# rp3a0-mini-hdmi.net
KiCad netlist of a schematic drawn in Altium Designer
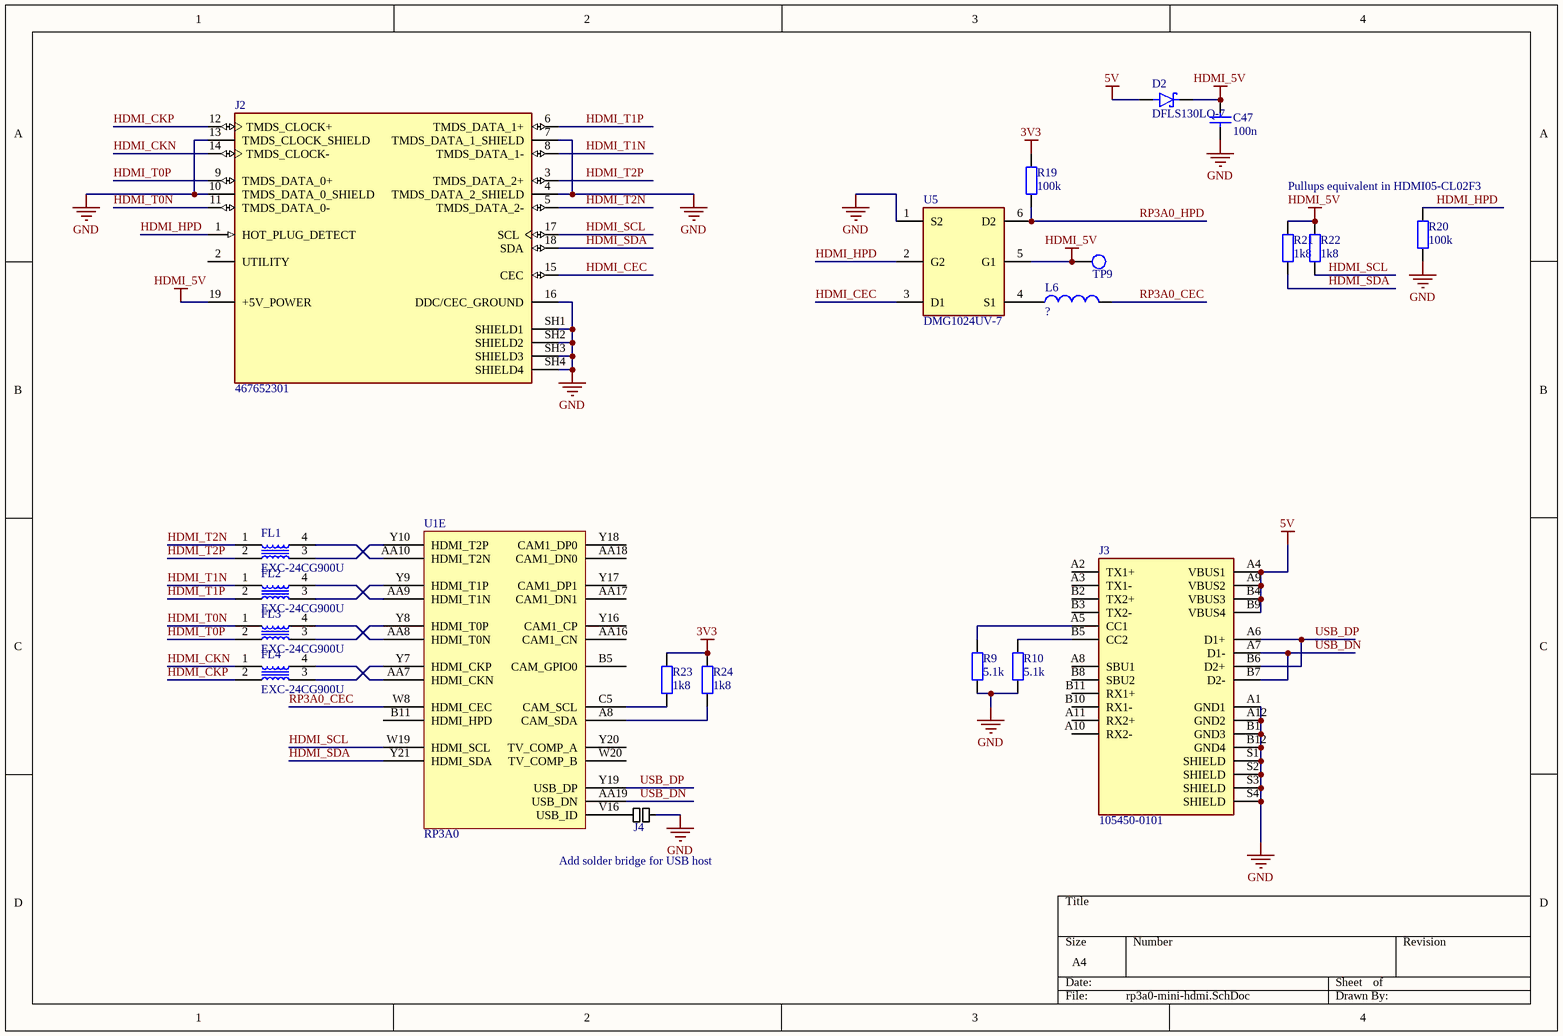
[diagram p0: rp3a0-mini-hdmi.SchDoc]

(export (version "E")
  (design (tool "Eeschema 10.0.6"))
  (components
    (comp (ref "C47")
      (value "100n")
      (footprint "0402")
      (description "Capacitor")
      (fields (field (name "Comment") "Cap"))
      (libsource (lib "custom-lib") (part "CAP-NONPOL"))
    )
    (comp (ref "D2")
      (value "DFLS130LQ-7")
      (footprint "DIO_DFLS130LQ-7")
      (description "Diode Schottky 1A 30V PowerDI 123 ¦ Diodes Inc DFLS130LQ-7")
      (fields (field (name "MF") "Diodes Inc.") (field (name "MP") "DFLS1100-7"))
      (libsource (lib "custom-lib") (part "DFLS130LQ-7"))
    )
    (comp (ref "FL1")
      (value "EXC-24CG900U")
      (footprint "FIL_EXC24CB102U")
      (fields (field (name "MP") "EXC24CG900U") (field (name "MF") "Panasonic"))
      (libsource (lib "panasonic") (part "EXC-24CG900U"))
    )
    (comp (ref "FL2")
      (value "EXC-24CG900U")
      (footprint "FIL_EXC24CB102U")
      (fields (field (name "MP") "EXC24CG900U") (field (name "MF") "Panasonic"))
      (libsource (lib "panasonic") (part "EXC-24CG900U"))
    )
    (comp (ref "FL3")
      (value "EXC-24CG900U")
      (footprint "FIL_EXC24CB102U")
      (fields (field (name "MP") "EXC24CG900U") (field (name "MF") "Panasonic"))
      (libsource (lib "panasonic") (part "EXC-24CG900U"))
    )
    (comp (ref "FL4")
      (value "EXC-24CG900U")
      (footprint "FIL_EXC24CB102U")
      (fields (field (name "MP") "EXC24CG900U") (field (name "MF") "Panasonic"))
      (libsource (lib "panasonic") (part "EXC-24CG900U"))
    )
    (comp (ref "J2")
      (value "467652301")
      (footprint "MOLEX_467652301")
      (fields (field (name "MF") "Molex"))
      (libsource (lib "custom-lib") (part "467652301"))
    )
    (comp (ref "J3")
      (value "105450-0101")
      (footprint "MOLEX_105450-0101")
      (description "USB-C, USB 3.1 Gen 2, Receptacle Connector 24 Position Surface Mount, Right Angle; Through Hole")
      (fields (field (name "MF") "Molex") (field (name "DIGI-KEY_PART_NUMBER") "WM12856CT-ND"))
      (libsource (lib "custom-lib") (part "105450-0101"))
    )
    (comp (ref "J4")
      (value "SOLDER_PAD_OPEN")
      (footprint "SOLDER_PAD_OPEN")
      (description "Solder pads with no connection")
      (libsource (lib "custom-lib") (part "SOLDER_PAD_OPEN"))
    )
    (comp (ref "L6")
      (value "?")
      (footprint "0402")
      (description "Inductor SMD")
      (fields (field (name "Comment") "INDUCTOR"))
      (libsource (lib "custom-lib") (part "INDUCTOR"))
    )
    (comp (ref "R9")
      (value "5.1k")
      (footprint "RES-0402-SML")
      (description "Resistor")
      (fields (field (name "Comment") "Res SMD"))
      (libsource (lib "custom-lib") (part "Res SMD"))
    )
    (comp (ref "R10")
      (value "5.1k")
      (footprint "RES-0402-SML")
      (description "Resistor")
      (fields (field (name "Comment") "Res SMD"))
      (libsource (lib "custom-lib") (part "Res SMD"))
    )
    (comp (ref "R19")
      (value "100k")
      (footprint "RES-0402-SML")
      (description "Resistor")
      (fields (field (name "Comment") "Res SMD"))
      (libsource (lib "custom-lib") (part "Res SMD"))
    )
    (comp (ref "R20")
      (value "100k")
      (footprint "RES-0402-SML")
      (description "Resistor")
      (fields (field (name "Comment") "Res SMD"))
      (libsource (lib "custom-lib") (part "Res SMD"))
    )
    (comp (ref "R21")
      (value "1k8")
      (footprint "RES-0402-SML")
      (description "Resistor")
      (fields (field (name "Comment") "Res SMD"))
      (libsource (lib "custom-lib") (part "Res SMD"))
    )
    (comp (ref "R22")
      (value "1k8")
      (footprint "RES-0402-SML")
      (description "Resistor")
      (fields (field (name "Comment") "Res SMD"))
      (libsource (lib "custom-lib") (part "Res SMD"))
    )
    (comp (ref "R23")
      (value "1k8")
      (footprint "RES-0402-SML")
      (description "Resistor")
      (fields (field (name "Comment") "Res SMD"))
      (libsource (lib "custom-lib") (part "Res SMD"))
    )
    (comp (ref "R24")
      (value "1k8")
      (footprint "RES-0402-SML")
      (description "Resistor")
      (fields (field (name "Comment") "Res SMD"))
      (libsource (lib "custom-lib") (part "Res SMD"))
    )
    (comp (ref "TP9")
      (value "TEST_POINT")
      (footprint "TEST_POINT_1.2MM")
      (description "Test point")
      (libsource (lib "custom-lib") (part "TEST_POINT"))
    )
    (comp (ref "U1") (value "RP3A0") (footprint "RP3A0-BGA") (libsource (lib "rp3a0") (part "RP3A0")))
    (comp (ref "U5")
      (value "DMG1024UV-7")
      (footprint "SOT50P162X60-6N")
      (description "Dual N-Ch Enhancement MOSFET SOT-563 ¦ Diodes Inc DMG1024UV-7")
      (fields (field (name "MF") "Diodes Inc."))
      (libsource (lib "custom-lib") (part "DMG1024UV-7"))
    )
  )
  (nets
    (net (code "1") (name "/HDMI_CEC") (class "Default")
      (node (ref "J2") (pin "15") (pinfunction "CEC_15") (pintype "bidirectional"))
      (node (ref "U5") (pin "3") (pinfunction "D1_3") (pintype "passive"))
    )
    (net (code "2") (name "/HDMI_CKN") (class "Default")
      (node (ref "FL4") (pin "1") (pinfunction "1_1") (pintype "passive"))
      (node (ref "J2") (pin "14") (pinfunction "TMDS_CLOCK-_14") (pintype "bidirectional"))
    )
    (net (code "3") (name "/HDMI_CKP") (class "Default")
      (node (ref "FL4") (pin "2") (pinfunction "2_2") (pintype "passive"))
      (node (ref "J2") (pin "12") (pinfunction "TMDS_CLOCK+_12") (pintype "bidirectional"))
    )
    (net (code "4") (name "/HDMI_HPD") (class "Default")
      (node (ref "J2") (pin "1") (pinfunction "HOT_PLUG_DETECT_1") (pintype "input"))
      (node (ref "R20") (pin "2") (pinfunction "2_2") (pintype "passive"))
      (node (ref "U5") (pin "2") (pinfunction "G2_2") (pintype "passive"))
    )
    (net (code "5") (name "/HDMI_SCL") (class "Default")
      (node (ref "J2") (pin "17") (pinfunction "SCL_17") (pintype "bidirectional"))
      (node (ref "R22") (pin "1") (pinfunction "1_1") (pintype "passive"))
      (node (ref "U1") (pin "W19") (pinfunction "HDMI_SCL_W19") (pintype "passive"))
    )
    (net (code "6") (name "/HDMI_SDA") (class "Default")
      (node (ref "J2") (pin "18") (pinfunction "SDA_18") (pintype "bidirectional"))
      (node (ref "R21") (pin "1") (pinfunction "1_1") (pintype "passive"))
      (node (ref "U1") (pin "Y21") (pinfunction "HDMI_SDA_Y21") (pintype "passive"))
    )
    (net (code "7") (name "/HDMI_T0N") (class "Default")
      (node (ref "FL3") (pin "1") (pinfunction "1_1") (pintype "passive"))
      (node (ref "J2") (pin "11") (pinfunction "TMDS_DATA_0-_11") (pintype "bidirectional"))
    )
    (net (code "8") (name "/HDMI_T0P") (class "Default")
      (node (ref "FL3") (pin "2") (pinfunction "2_2") (pintype "passive"))
      (node (ref "J2") (pin "9") (pinfunction "TMDS_DATA_0+_9") (pintype "bidirectional"))
    )
    (net (code "9") (name "/HDMI_T1N") (class "Default")
      (node (ref "FL2") (pin "1") (pinfunction "1_1") (pintype "passive"))
      (node (ref "J2") (pin "8") (pinfunction "TMDS_DATA_1-_8") (pintype "bidirectional"))
    )
    (net (code "10") (name "/HDMI_T1P") (class "Default")
      (node (ref "FL2") (pin "2") (pinfunction "2_2") (pintype "passive"))
      (node (ref "J2") (pin "6") (pinfunction "TMDS_DATA_1+_6") (pintype "bidirectional"))
    )
    (net (code "11") (name "/HDMI_T2N") (class "Default")
      (node (ref "FL1") (pin "1") (pinfunction "1_1") (pintype "passive"))
      (node (ref "J2") (pin "5") (pinfunction "TMDS_DATA_2-_5") (pintype "bidirectional"))
    )
    (net (code "12") (name "/HDMI_T2P") (class "Default")
      (node (ref "FL1") (pin "2") (pinfunction "2_2") (pintype "passive"))
      (node (ref "J2") (pin "3") (pinfunction "TMDS_DATA_2+_3") (pintype "bidirectional"))
    )
    (net (code "13") (name "/RP3A0_CEC") (class "Default")
      (node (ref "L6") (pin "2") (pinfunction "2_2") (pintype "passive"))
      (node (ref "U1") (pin "W8") (pinfunction "HDMI_CEC_W8") (pintype "passive"))
    )
    (net (code "14") (name "/RP3A0_HPD") (class "Default")
      (node (ref "R19") (pin "1") (pinfunction "1_1") (pintype "passive"))
      (node (ref "U5") (pin "6") (pinfunction "D2_6") (pintype "passive"))
    )
    (net (code "15") (name "/USB_DN") (class "Default")
      (node (ref "J3") (pin "A7") (pinfunction "D1-_A7") (pintype "passive"))
      (node (ref "J3") (pin "B7") (pinfunction "D2-_B7") (pintype "passive"))
      (node (ref "U1") (pin "AA19") (pinfunction "USB_DN_AA19") (pintype "passive"))
    )
    (net (code "16") (name "/USB_DP") (class "Default")
      (node (ref "J3") (pin "A6") (pinfunction "D1+_A6") (pintype "passive"))
      (node (ref "J3") (pin "B6") (pinfunction "D2+_B6") (pintype "passive"))
      (node (ref "U1") (pin "Y19") (pinfunction "USB_DP_Y19") (pintype "passive"))
    )
    (net (code "17") (name "3V3") (class "Default")
      (node (ref "R19") (pin "2") (pinfunction "2_2") (pintype "passive"))
      (node (ref "R23") (pin "2") (pinfunction "2_2") (pintype "passive"))
      (node (ref "R24") (pin "2") (pinfunction "2_2") (pintype "passive"))
    )
    (net (code "18") (name "5V") (class "Default")
      (node (ref "D2") (pin "A") (pinfunction "A_A") (pintype "passive"))
      (node (ref "J3") (pin "A4") (pinfunction "VBUS1_A4") (pintype "passive"))
      (node (ref "J3") (pin "A9") (pinfunction "VBUS2_A9") (pintype "passive"))
      (node (ref "J3") (pin "B4") (pinfunction "VBUS3_B4") (pintype "passive"))
      (node (ref "J3") (pin "B9") (pinfunction "VBUS4_B9") (pintype "passive"))
    )
    (net (code "19") (name "GND") (class "Default")
      (node (ref "C47") (pin "1") (pinfunction "1_1") (pintype "passive"))
      (node (ref "J2") (pin "10") (pinfunction "TMDS_DATA_0_SHIELD_10") (pintype "passive"))
      (node (ref "J2") (pin "13") (pinfunction "TMDS_CLOCK_SHIELD_13") (pintype "passive"))
      (node (ref "J2") (pin "16") (pinfunction "DDC/CEC_GROUND_16") (pintype "power_in"))
      (node (ref "J2") (pin "4") (pinfunction "TMDS_DATA_2_SHIELD_4") (pintype "passive"))
      (node (ref "J2") (pin "7") (pinfunction "TMDS_DATA_1_SHIELD_7") (pintype "passive"))
      (node (ref "J2") (pin "SH1") (pinfunction "SHIELD1_SH1") (pintype "passive"))
      (node (ref "J2") (pin "SH2") (pinfunction "SHIELD2_SH2") (pintype "passive"))
      (node (ref "J2") (pin "SH3") (pinfunction "SHIELD3_SH3") (pintype "passive"))
      (node (ref "J2") (pin "SH4") (pinfunction "SHIELD4_SH4") (pintype "passive"))
      (node (ref "J3") (pin "A1") (pinfunction "GND1_A1") (pintype "passive"))
      (node (ref "J3") (pin "A12") (pinfunction "GND2_A12") (pintype "passive"))
      (node (ref "J3") (pin "B1") (pinfunction "GND3_B1") (pintype "passive"))
      (node (ref "J3") (pin "B12") (pinfunction "GND4_B12") (pintype "passive"))
      (node (ref "J3") (pin "S1") (pinfunction "SHIELD_S1") (pintype "passive"))
      (node (ref "J3") (pin "S2") (pinfunction "SHIELD_S2") (pintype "passive"))
      (node (ref "J3") (pin "S3") (pinfunction "SHIELD_S3") (pintype "passive"))
      (node (ref "J3") (pin "S4") (pinfunction "SHIELD_S4") (pintype "passive"))
      (node (ref "J4") (pin "2") (pintype "passive"))
      (node (ref "R10") (pin "1") (pinfunction "1_1") (pintype "passive"))
      (node (ref "R20") (pin "1") (pinfunction "1_1") (pintype "passive"))
      (node (ref "R9") (pin "1") (pinfunction "1_1") (pintype "passive"))
      (node (ref "U5") (pin "1") (pinfunction "S2_1") (pintype "passive"))
    )
    (net (code "20") (name "HDMI_5V") (class "Default")
      (node (ref "C47") (pin "2") (pinfunction "2_2") (pintype "passive"))
      (node (ref "D2") (pin "K") (pinfunction "K_K") (pintype "passive"))
      (node (ref "J2") (pin "19") (pinfunction "+5V_POWER_19") (pintype "power_in"))
      (node (ref "R21") (pin "2") (pinfunction "2_2") (pintype "passive"))
      (node (ref "R22") (pin "2") (pinfunction "2_2") (pintype "passive"))
      (node (ref "TP9") (pin "TP") (pintype "passive"))
      (node (ref "U5") (pin "5") (pinfunction "G1_5") (pintype "passive"))
    )
    (net (code "21") (name "Net-(J3-CC1)") (class "Default")
      (node (ref "J3") (pin "A5") (pinfunction "CC1_A5") (pintype "passive"))
      (node (ref "R9") (pin "2") (pinfunction "2_2") (pintype "passive"))
    )
    (net (code "22") (name "Net-(J3-CC2)") (class "Default")
      (node (ref "J3") (pin "B5") (pinfunction "CC2_B5") (pintype "passive"))
      (node (ref "R10") (pin "2") (pinfunction "2_2") (pintype "passive"))
    )
    (net (code "23") (name "Net-(U1E-CAM_SCL)") (class "Default")
      (node (ref "R23") (pin "1") (pinfunction "1_1") (pintype "passive"))
      (node (ref "U1") (pin "C5") (pinfunction "CAM_SCL_C5") (pintype "passive"))
    )
    (net (code "24") (name "Net-(U1E-CAM_SDA)") (class "Default")
      (node (ref "R24") (pin "1") (pinfunction "1_1") (pintype "passive"))
      (node (ref "U1") (pin "A8") (pinfunction "CAM_SDA_A8") (pintype "passive"))
    )
    (net (code "25") (name "Net-(U1E-HDMI_CKN)") (class "Default")
      (node (ref "FL4") (pin "4") (pinfunction "4_4") (pintype "passive"))
      (node (ref "U1") (pin "AA7") (pinfunction "HDMI_CKN_AA7") (pintype "passive"))
    )
    (net (code "26") (name "Net-(U1E-HDMI_CKP)") (class "Default")
      (node (ref "FL4") (pin "3") (pinfunction "3_3") (pintype "passive"))
      (node (ref "U1") (pin "Y7") (pinfunction "HDMI_CKP_Y7") (pintype "passive"))
    )
    (net (code "27") (name "Net-(U1E-HDMI_T0N)") (class "Default")
      (node (ref "FL3") (pin "4") (pinfunction "4_4") (pintype "passive"))
      (node (ref "U1") (pin "AA8") (pinfunction "HDMI_T0N_AA8") (pintype "passive"))
    )
    (net (code "28") (name "Net-(U1E-HDMI_T0P)") (class "Default")
      (node (ref "FL3") (pin "3") (pinfunction "3_3") (pintype "passive"))
      (node (ref "U1") (pin "Y8") (pinfunction "HDMI_T0P_Y8") (pintype "passive"))
    )
    (net (code "29") (name "Net-(U1E-HDMI_T1N)") (class "Default")
      (node (ref "FL2") (pin "4") (pinfunction "4_4") (pintype "passive"))
      (node (ref "U1") (pin "AA9") (pinfunction "HDMI_T1N_AA9") (pintype "passive"))
    )
    (net (code "30") (name "Net-(U1E-HDMI_T1P)") (class "Default")
      (node (ref "FL2") (pin "3") (pinfunction "3_3") (pintype "passive"))
      (node (ref "U1") (pin "Y9") (pinfunction "HDMI_T1P_Y9") (pintype "passive"))
    )
    (net (code "31") (name "Net-(U1E-HDMI_T2N)") (class "Default")
      (node (ref "FL1") (pin "4") (pinfunction "4_4") (pintype "passive"))
      (node (ref "U1") (pin "AA10") (pinfunction "HDMI_T2N_AA10") (pintype "passive"))
    )
    (net (code "32") (name "Net-(U1E-HDMI_T2P)") (class "Default")
      (node (ref "FL1") (pin "3") (pinfunction "3_3") (pintype "passive"))
      (node (ref "U1") (pin "Y10") (pinfunction "HDMI_T2P_Y10") (pintype "passive"))
    )
    (net (code "33") (name "Net-(U1E-USB_ID)") (class "Default")
      (node (ref "J4") (pin "1") (pintype "passive"))
      (node (ref "U1") (pin "V16") (pinfunction "USB_ID_V16") (pintype "passive"))
    )
    (net (code "34") (name "Net-(U5-S1)") (class "Default")
      (node (ref "L6") (pin "1") (pinfunction "1_1") (pintype "passive"))
      (node (ref "U5") (pin "4") (pinfunction "S1_4") (pintype "passive"))
    )
    (net (code "35") (name "unconnected-(J2-UTILITY-Pad2)") (class "Default")
      (node (ref "J2") (pin "2") (pinfunction "UTILITY_2") (pintype "passive"))
    )
    (net (code "36") (name "unconnected-(J3-RX1+-PadB11)") (class "Default")
      (node (ref "J3") (pin "B11") (pinfunction "RX1+_B11") (pintype "passive"))
    )
    (net (code "37") (name "unconnected-(J3-RX1--PadB10)") (class "Default")
      (node (ref "J3") (pin "B10") (pinfunction "RX1-_B10") (pintype "passive"))
    )
    (net (code "38") (name "unconnected-(J3-RX2+-PadA11)") (class "Default")
      (node (ref "J3") (pin "A11") (pinfunction "RX2+_A11") (pintype "passive"))
    )
    (net (code "39") (name "unconnected-(J3-RX2--PadA10)") (class "Default")
      (node (ref "J3") (pin "A10") (pinfunction "RX2-_A10") (pintype "passive"))
    )
    (net (code "40") (name "unconnected-(J3-SBU1-PadA8)") (class "Default")
      (node (ref "J3") (pin "A8") (pinfunction "SBU1_A8") (pintype "passive"))
    )
    (net (code "41") (name "unconnected-(J3-SBU2-PadB8)") (class "Default")
      (node (ref "J3") (pin "B8") (pinfunction "SBU2_B8") (pintype "passive"))
    )
    (net (code "42") (name "unconnected-(J3-TX1+-PadA2)") (class "Default")
      (node (ref "J3") (pin "A2") (pinfunction "TX1+_A2") (pintype "passive"))
    )
    (net (code "43") (name "unconnected-(J3-TX1--PadA3)") (class "Default")
      (node (ref "J3") (pin "A3") (pinfunction "TX1-_A3") (pintype "passive"))
    )
    (net (code "44") (name "unconnected-(J3-TX2+-PadB2)") (class "Default")
      (node (ref "J3") (pin "B2") (pinfunction "TX2+_B2") (pintype "passive"))
    )
    (net (code "45") (name "unconnected-(J3-TX2--PadB3)") (class "Default")
      (node (ref "J3") (pin "B3") (pinfunction "TX2-_B3") (pintype "passive"))
    )
    (net (code "46") (name "unconnected-(U1E-CAM1_CN-PadAA16)") (class "Default")
      (node (ref "U1") (pin "AA16") (pinfunction "CAM1_CN_AA16") (pintype "passive"))
    )
    (net (code "47") (name "unconnected-(U1E-CAM1_CP-PadY16)") (class "Default")
      (node (ref "U1") (pin "Y16") (pinfunction "CAM1_CP_Y16") (pintype "passive"))
    )
    (net (code "48") (name "unconnected-(U1E-CAM1_DN0-PadAA18)") (class "Default")
      (node (ref "U1") (pin "AA18") (pinfunction "CAM1_DN0_AA18") (pintype "passive"))
    )
    (net (code "49") (name "unconnected-(U1E-CAM1_DN1-PadAA17)") (class "Default")
      (node (ref "U1") (pin "AA17") (pinfunction "CAM1_DN1_AA17") (pintype "passive"))
    )
    (net (code "50") (name "unconnected-(U1E-CAM1_DP0-PadY18)") (class "Default")
      (node (ref "U1") (pin "Y18") (pinfunction "CAM1_DP0_Y18") (pintype "passive"))
    )
    (net (code "51") (name "unconnected-(U1E-CAM1_DP1-PadY17)") (class "Default")
      (node (ref "U1") (pin "Y17") (pinfunction "CAM1_DP1_Y17") (pintype "passive"))
    )
    (net (code "52") (name "unconnected-(U1E-CAM_GPIO0-PadB5)") (class "Default")
      (node (ref "U1") (pin "B5") (pinfunction "CAM_GPIO0_B5") (pintype "passive"))
    )
    (net (code "53") (name "unconnected-(U1E-HDMI_HPD-PadB11)") (class "Default")
      (node (ref "U1") (pin "B11") (pinfunction "HDMI_HPD_B11") (pintype "passive"))
    )
    (net (code "54") (name "unconnected-(U1E-TV_COMP_A-PadY20)") (class "Default")
      (node (ref "U1") (pin "Y20") (pinfunction "TV_COMP_A_Y20") (pintype "passive"))
    )
    (net (code "55") (name "unconnected-(U1E-TV_COMP_B-PadW20)") (class "Default")
      (node (ref "U1") (pin "W20") (pinfunction "TV_COMP_B_W20") (pintype "passive"))
    )
  )
)
